# Raspberry_output_for_PWM_based_Fan_drive.net
KiCad netlist of a schematic drawn in EAGLE
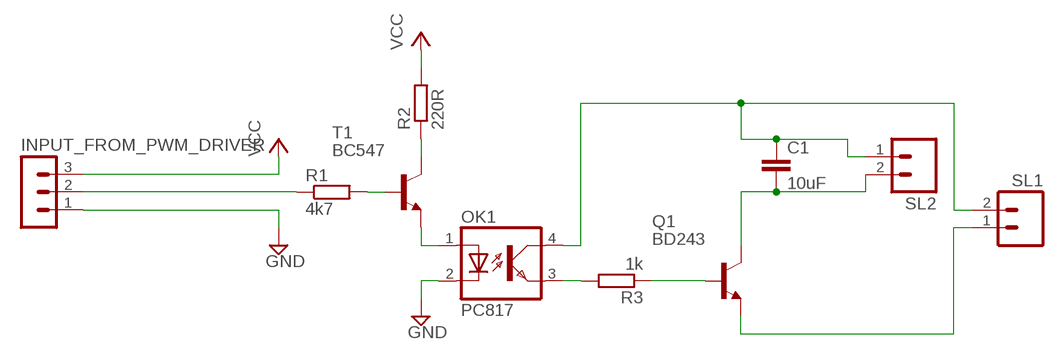
[diagram p0: schematic, sheet 1]

(export (version "E")
  (design (tool "Eeschema 10.0.6"))
  (components
    (comp (ref "C1")
      (value "10uF")
      (footprint "eagle-import:C2.5-5")
      (libsource (lib "eagle-import") (part "C2.5/5"))
    )
    (comp (ref "INPUT_FROM_PWM_DRIVER")
      (value "MA03-1")
      (footprint "eagle-import:MA03-1")
      (libsource (lib "eagle-import") (part "MA03-1"))
    )
    (comp (ref "OK1")
      (value "PC817")
      (footprint "eagle-import:DIL04")
      (libsource (lib "eagle-import") (part "PC817"))
    )
    (comp (ref "Q1")
      (value "BD243")
      (footprint "eagle-import:TO220")
      (libsource (lib "eagle-import") (part "BD243"))
    )
    (comp (ref "R1")
      (value "4k7")
      (footprint "eagle-import:0207_10")
      (libsource (lib "eagle-import") (part "R-EU_0207/10"))
    )
    (comp (ref "R2")
      (value "220R")
      (footprint "eagle-import:0207_10")
      (libsource (lib "eagle-import") (part "R-EU_0207/10"))
    )
    (comp (ref "R3")
      (value "1k")
      (footprint "eagle-import:0207_10")
      (libsource (lib "eagle-import") (part "R-EU_0207/10"))
    )
    (comp (ref "SL1")
      (value "MA02")
      (footprint "eagle-import:02PA")
      (libsource (lib "eagle-import") (part "MA02"))
    )
    (comp (ref "SL2")
      (value "MA02")
      (footprint "eagle-import:02PA")
      (libsource (lib "eagle-import") (part "MA02"))
    )
    (comp (ref "T1")
      (value "BC547")
      (footprint "eagle-import:TO92")
      (libsource (lib "eagle-import") (part "BC547"))
    )
  )
  (nets
    (net (code "1") (name "GND") (class "Default")
      (node (ref "INPUT_FROM_PWM_DRIVER") (pin "1") (pinfunction "1_1") (pintype "passive"))
      (node (ref "OK1") (pin "2") (pinfunction "C_2") (pintype "passive"))
    )
    (net (code "2") (name "Net-(INPUT_FROM_PWM_DRIVER-Pad2)") (class "Default")
      (node (ref "INPUT_FROM_PWM_DRIVER") (pin "2") (pinfunction "2_2") (pintype "passive"))
      (node (ref "R1") (pin "1") (pinfunction "1_1") (pintype "passive"))
    )
    (net (code "3") (name "Net-(OK1-A)") (class "Default")
      (node (ref "OK1") (pin "1") (pinfunction "A_1") (pintype "passive"))
      (node (ref "T1") (pin "1") (pinfunction "E_1") (pintype "passive"))
    )
    (net (code "4") (name "Net-(OK1-COL)") (class "Default")
      (node (ref "C1") (pin "1") (pinfunction "1_1") (pintype "passive"))
      (node (ref "OK1") (pin "4") (pinfunction "COL_4") (pintype "passive"))
      (node (ref "SL1") (pin "2") (pinfunction "2_2") (pintype "passive"))
      (node (ref "SL2") (pin "1") (pinfunction "1_1") (pintype "passive"))
    )
    (net (code "5") (name "Net-(OK1-EMIT)") (class "Default")
      (node (ref "OK1") (pin "3") (pinfunction "EMIT_3") (pintype "passive"))
      (node (ref "R3") (pin "2") (pinfunction "2_2") (pintype "passive"))
    )
    (net (code "6") (name "Net-(Q1-B)") (class "Default")
      (node (ref "Q1") (pin "1") (pinfunction "B_1") (pintype "passive"))
      (node (ref "R3") (pin "1") (pinfunction "1_1") (pintype "passive"))
    )
    (net (code "7") (name "Net-(Q1-C)") (class "Default")
      (node (ref "C1") (pin "2") (pinfunction "2_2") (pintype "passive"))
      (node (ref "Q1") (pin "2") (pinfunction "C_2") (pintype "passive"))
      (node (ref "SL2") (pin "2") (pinfunction "2_2") (pintype "passive"))
    )
    (net (code "8") (name "Net-(Q1-E)") (class "Default")
      (node (ref "Q1") (pin "3") (pinfunction "E_3") (pintype "passive"))
      (node (ref "SL1") (pin "1") (pinfunction "1_1") (pintype "passive"))
    )
    (net (code "9") (name "Net-(T1-B)") (class "Default")
      (node (ref "R1") (pin "2") (pinfunction "2_2") (pintype "passive"))
      (node (ref "T1") (pin "2") (pinfunction "B_2") (pintype "passive"))
    )
    (net (code "10") (name "Net-(T1-C)") (class "Default")
      (node (ref "R2") (pin "1") (pinfunction "1_1") (pintype "passive"))
      (node (ref "T1") (pin "3") (pinfunction "C_3") (pintype "passive"))
    )
    (net (code "11") (name "VCC") (class "Default")
      (node (ref "INPUT_FROM_PWM_DRIVER") (pin "3") (pinfunction "3_3") (pintype "passive"))
      (node (ref "R2") (pin "2") (pinfunction "2_2") (pintype "passive"))
    )
  )
)
